# Thermal.net
KiCad netlist of a schematic drawn in Altium Designer
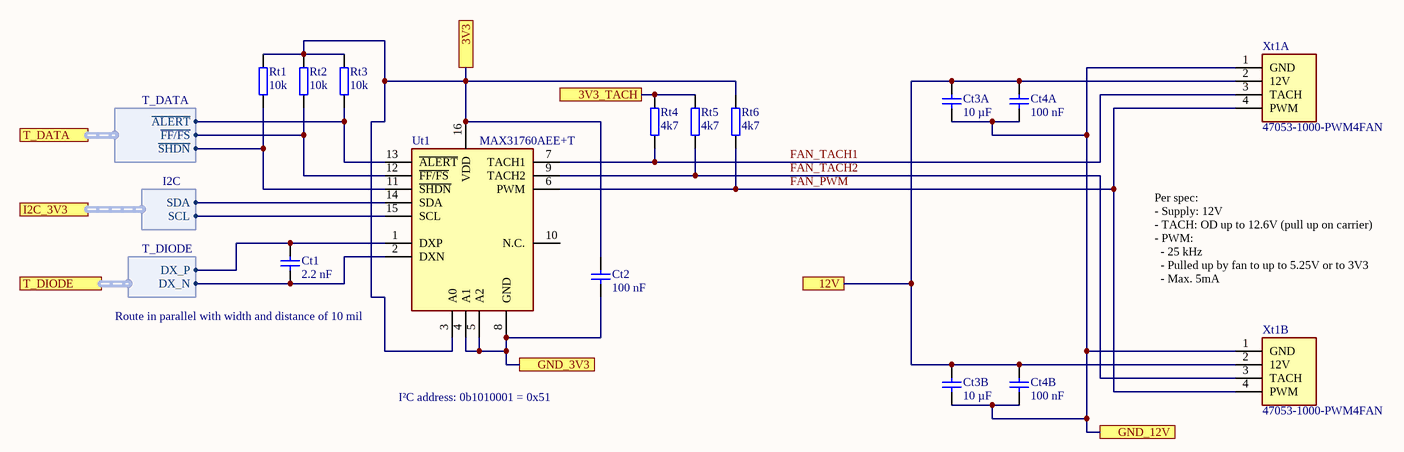
[diagram p0: Thermal.SchDoc]

(export (version "E")
  (design (tool "Eeschema 10.0.6"))
  (components
    (comp (ref "Ct1")
      (value "2.2 nF")
      (footprint "C_0603_TE")
      (description "Generic capacitor")
      (fields
        (field (name "MANUFACTURER PART NUMBER") "UZgen_C_0603_2.2nF_50V_X7R")
        (field (name "MANUFACTURER") "UZgen")
        (field (name "CREATED FROM") "UZgenTool")
      )
      (libsource (lib "user") (part "CAP-NP"))
    )
    (comp (ref "Ct2")
      (value "100 nF")
      (footprint "C_0603_TE")
      (description "Generic capacitor")
      (fields
        (field (name "MANUFACTURER PART NUMBER") "UZgen_C_0603_100nF_50V_X7R")
        (field (name "MANUFACTURER") "UZgen")
        (field (name "CREATED FROM") "AGeiger")
      )
      (libsource (lib "user") (part "CAP-NP"))
    )
    (comp (ref "Ct3A")
      (value "10 µF")
      (footprint "C_1206_TE")
      (description "Generic capacitor")
      (fields
        (field (name "MANUFACTURER PART NUMBER") "UZgen_C_1206_10uF_50V_X7R")
        (field (name "MANUFACTURER") "UZgen")
        (field (name "CREATED FROM") "MGeier")
      )
      (libsource (lib "user") (part "CAP-NP"))
    )
    (comp (ref "Ct3B")
      (value "10 µF")
      (footprint "C_1206_TE")
      (description "Generic capacitor")
      (fields
        (field (name "MANUFACTURER PART NUMBER") "UZgen_C_1206_10uF_50V_X7R")
        (field (name "MANUFACTURER") "UZgen")
        (field (name "CREATED FROM") "MGeier")
      )
      (libsource (lib "user") (part "CAP-NP"))
    )
    (comp (ref "Ct4A")
      (value "100 nF")
      (footprint "C_0603_TE")
      (description "Generic capacitor")
      (fields
        (field (name "MANUFACTURER PART NUMBER") "UZgen_C_0603_100nF_50V_X7R")
        (field (name "MANUFACTURER") "UZgen")
        (field (name "CREATED FROM") "AGeiger")
      )
      (libsource (lib "user") (part "CAP-NP"))
    )
    (comp (ref "Ct4B")
      (value "100 nF")
      (footprint "C_0603_TE")
      (description "Generic capacitor")
      (fields
        (field (name "MANUFACTURER PART NUMBER") "UZgen_C_0603_100nF_50V_X7R")
        (field (name "MANUFACTURER") "UZgen")
        (field (name "CREATED FROM") "AGeiger")
      )
      (libsource (lib "user") (part "CAP-NP"))
    )
    (comp (ref "Rt1")
      (value "10k")
      (footprint "R_0603_TE")
      (description "Generic resistor")
      (fields
        (field (name "MANUFACTURER PART NUMBER") "UZgen_R_0603_10k")
        (field (name "MANUFACTURER") "UZgen")
        (field (name "CREATED FROM") "AGeiger")
      )
      (libsource (lib "user") (part "RES"))
    )
    (comp (ref "Rt2")
      (value "10k")
      (footprint "R_0603_TE")
      (description "Generic resistor")
      (fields
        (field (name "MANUFACTURER PART NUMBER") "UZgen_R_0603_10k")
        (field (name "MANUFACTURER") "UZgen")
        (field (name "CREATED FROM") "AGeiger")
      )
      (libsource (lib "user") (part "RES"))
    )
    (comp (ref "Rt3")
      (value "10k")
      (footprint "R_0603_TE")
      (description "Generic resistor")
      (fields
        (field (name "MANUFACTURER PART NUMBER") "UZgen_R_0603_10k")
        (field (name "MANUFACTURER") "UZgen")
        (field (name "CREATED FROM") "AGeiger")
      )
      (libsource (lib "user") (part "RES"))
    )
    (comp (ref "Rt4")
      (value "4k7")
      (footprint "R_0603_TE")
      (description "Generic resistor")
      (fields
        (field (name "MANUFACTURER PART NUMBER") "UZgen_R_0603_4k7")
        (field (name "MANUFACTURER") "UZgen")
        (field (name "CREATED FROM") "UZgenTool")
      )
      (libsource (lib "user") (part "RES"))
    )
    (comp (ref "Rt5")
      (value "4k7")
      (footprint "R_0603_TE")
      (description "Generic resistor")
      (fields
        (field (name "MANUFACTURER PART NUMBER") "UZgen_R_0603_4k7")
        (field (name "MANUFACTURER") "UZgen")
        (field (name "CREATED FROM") "UZgenTool")
      )
      (libsource (lib "user") (part "RES"))
    )
    (comp (ref "Rt6")
      (value "4k7")
      (footprint "R_0603_TE")
      (description "Generic resistor")
      (fields
        (field (name "MANUFACTURER PART NUMBER") "UZgen_R_0603_4k7")
        (field (name "MANUFACTURER") "UZgen")
        (field (name "CREATED FROM") "UZgenTool")
      )
      (libsource (lib "user") (part "RES"))
    )
    (comp (ref "Ut1")
      (value "MAX31760AEE+T")
      (footprint "SOP64P602X175-16N")
      (description "Motor/Motion/Ignition Controllers & Drivers Fan Speed Controller with LUT t&r")
      (fields
        (field (name "MANUFACTURER") "Analog Devices Inc.")
        (field (name "LCSC PART NUMBER") "C3031567")
        (field (name "CREATED FROM") "FRosner")
      )
      (libsource (lib "user") (part "MAX31760AEE+"))
    )
    (comp (ref "Xt1A")
      (value "47053-1000-PWM4FAN")
      (footprint "470531000")
      (description "Headers & Wire Housings 4P VERT HDR W/FL")
      (fields
        (field (name "MANUFACTURER_PART_NUMBER") "47053-1000")
        (field (name "MOUSER PART NUMBER") "538-47053-1000")
        (field (name "CREATED FROM") "FRosner")
      )
      (libsource (lib "user") (part "470531000-PWM4FAN"))
    )
    (comp (ref "Xt1B")
      (value "47053-1000-PWM4FAN")
      (footprint "470531000")
      (description "Headers & Wire Housings 4P VERT HDR W/FL")
      (fields
        (field (name "MANUFACTURER_PART_NUMBER") "47053-1000")
        (field (name "MOUSER PART NUMBER") "538-47053-1000")
        (field (name "CREATED FROM") "FRosner")
      )
      (libsource (lib "user") (part "470531000-PWM4FAN"))
    )
  )
  (nets
    (net (code "4") (name "/3V3") (class "Default")
      (node (ref "Ct2") (pin "2") (pinfunction "2_2") (pintype "passive"))
      (node (ref "Rt1") (pin "2") (pinfunction "2_2") (pintype "passive"))
      (node (ref "Rt2") (pin "2") (pinfunction "2_2") (pintype "passive"))
      (node (ref "Rt3") (pin "2") (pinfunction "2_2") (pintype "passive"))
      (node (ref "Rt6") (pin "2") (pinfunction "2_2") (pintype "passive"))
      (node (ref "Ut1") (pin "16") (pinfunction "VDD_16") (pintype "passive"))
      (node (ref "Ut1") (pin "3") (pinfunction "A0_3") (pintype "passive"))
    )
    (net (code "5") (name "/3V3_TACH") (class "Default")
      (node (ref "Rt4") (pin "2") (pinfunction "2_2") (pintype "passive"))
      (node (ref "Rt5") (pin "2") (pinfunction "2_2") (pintype "passive"))
    )
    (net (code "6") (name "/12V") (class "Default")
      (node (ref "Ct3A") (pin "2") (pinfunction "2_2") (pintype "passive"))
      (node (ref "Ct3B") (pin "2") (pinfunction "2_2") (pintype "passive"))
      (node (ref "Ct4A") (pin "2") (pinfunction "2_2") (pintype "passive"))
      (node (ref "Ct4B") (pin "2") (pinfunction "2_2") (pintype "passive"))
      (node (ref "Xt1A") (pin "2") (pinfunction "12V_2") (pintype "passive"))
      (node (ref "Xt1B") (pin "2") (pinfunction "12V_2") (pintype "passive"))
    )
    (net (code "7") (name "/DX_N") (class "Default")
      (node (ref "Ct1") (pin "1") (pinfunction "1_1") (pintype "passive"))
      (node (ref "Ut1") (pin "2") (pinfunction "DXN_2") (pintype "passive"))
    )
    (net (code "8") (name "/DX_P") (class "Default")
      (node (ref "Ct1") (pin "2") (pinfunction "2_2") (pintype "passive"))
      (node (ref "Ut1") (pin "1") (pinfunction "DXP_1") (pintype "passive"))
    )
    (net (code "9") (name "/FAN_PWM") (class "Default")
      (node (ref "Rt6") (pin "1") (pinfunction "1_1") (pintype "passive"))
      (node (ref "Ut1") (pin "6") (pinfunction "PWM_6") (pintype "passive"))
      (node (ref "Xt1A") (pin "4") (pinfunction "PWM_4") (pintype "passive"))
      (node (ref "Xt1B") (pin "4") (pinfunction "PWM_4") (pintype "passive"))
    )
    (net (code "10") (name "/FAN_TACH1") (class "Default")
      (node (ref "Rt4") (pin "1") (pinfunction "1_1") (pintype "passive"))
      (node (ref "Ut1") (pin "7") (pinfunction "TACH1_7") (pintype "passive"))
      (node (ref "Xt1A") (pin "3") (pinfunction "TACH_3") (pintype "passive"))
    )
    (net (code "11") (name "/FAN_TACH2") (class "Default")
      (node (ref "Rt5") (pin "1") (pinfunction "1_1") (pintype "passive"))
      (node (ref "Ut1") (pin "9") (pinfunction "TACH2_9") (pintype "passive"))
      (node (ref "Xt1B") (pin "3") (pinfunction "TACH_3") (pintype "passive"))
    )
    (net (code "12") (name "/GND_3V3") (class "Default")
      (node (ref "Ct2") (pin "1") (pinfunction "1_1") (pintype "passive"))
      (node (ref "Ut1") (pin "4") (pinfunction "A1_4") (pintype "passive"))
      (node (ref "Ut1") (pin "5") (pinfunction "A2_5") (pintype "passive"))
      (node (ref "Ut1") (pin "8") (pinfunction "GND_8") (pintype "passive"))
    )
    (net (code "13") (name "/GND_12V") (class "Default")
      (node (ref "Ct3A") (pin "1") (pinfunction "1_1") (pintype "passive"))
      (node (ref "Ct3B") (pin "1") (pinfunction "1_1") (pintype "passive"))
      (node (ref "Ct4A") (pin "1") (pinfunction "1_1") (pintype "passive"))
      (node (ref "Ct4B") (pin "1") (pinfunction "1_1") (pintype "passive"))
      (node (ref "Xt1A") (pin "1") (pinfunction "GND_1") (pintype "passive"))
      (node (ref "Xt1B") (pin "1") (pinfunction "GND_1") (pintype "passive"))
    )
    (net (code "14") (name "/SCL") (class "Default")
      (node (ref "Ut1") (pin "15") (pinfunction "SCL_15") (pintype "passive"))
    )
    (net (code "15") (name "/SDA") (class "Default")
      (node (ref "Ut1") (pin "14") (pinfunction "SDA_14") (pintype "passive"))
    )
    (net (code "19") (name "/~{ALERT}") (class "Default")
      (node (ref "Rt3") (pin "1") (pinfunction "1_1") (pintype "passive"))
      (node (ref "Ut1") (pin "13") (pinfunction "~{ALERT}_13") (pintype "passive"))
    )
    (net (code "20") (name "/~{FF{slash}FS}") (class "Default")
      (node (ref "Rt2") (pin "1") (pinfunction "1_1") (pintype "passive"))
      (node (ref "Ut1") (pin "12") (pinfunction "~{FF/FS}_12") (pintype "passive"))
    )
    (net (code "21") (name "/~{SHDN}") (class "Default")
      (node (ref "Rt1") (pin "1") (pinfunction "1_1") (pintype "passive"))
      (node (ref "Ut1") (pin "11") (pinfunction "~{SHDN}_11") (pintype "passive"))
    )
    (net (code "22") (name "unconnected-(Ut1-N.C.-Pad10)") (class "Default")
      (node (ref "Ut1") (pin "10") (pinfunction "N.C._10") (pintype "passive"))
    )
  )
)
